# main.net
KiCad netlist of a schematic drawn in Altium Designer
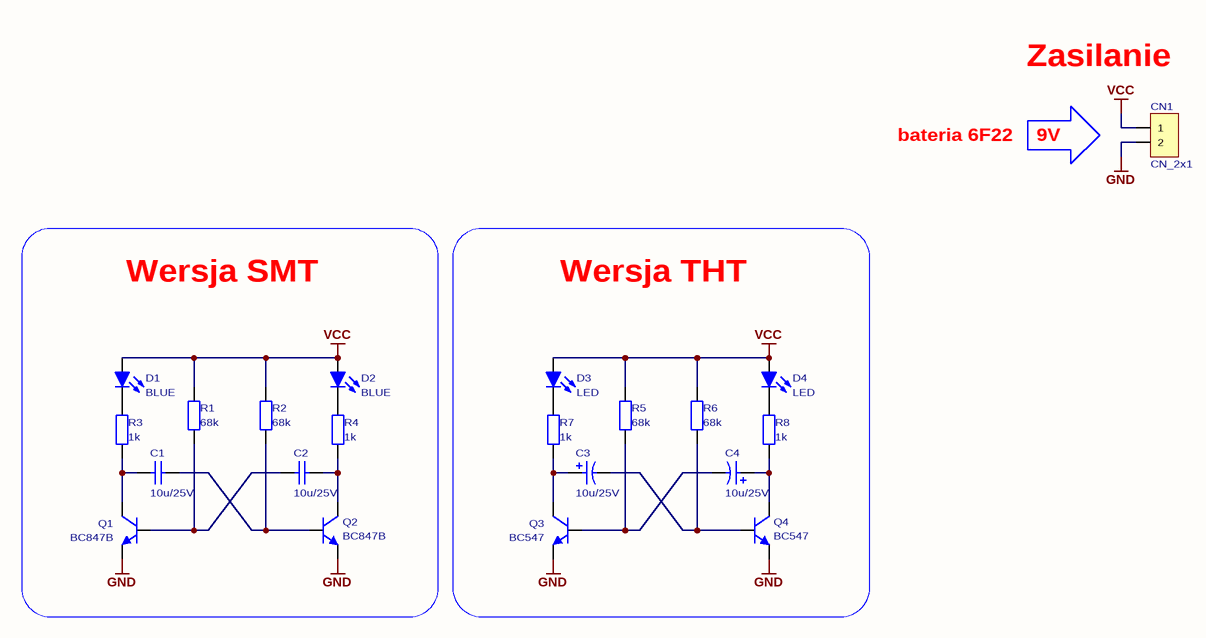
[diagram p0: main.SchDoc]

(export (version "E")
  (design (tool "Eeschema 10.0.6"))
  (components
    (comp (ref "C1")
      (value "10u/25V")
      (footprint "C1206")
      (description "Capacitor")
      (libsource (lib "capacitors") (part "Cap"))
    )
    (comp (ref "C2")
      (value "10u/25V")
      (footprint "C1206")
      (description "Capacitor")
      (libsource (lib "capacitors") (part "Cap"))
    )
    (comp (ref "C3")
      (value "10u/25V")
      (footprint "CE5x11-2")
      (description "Polarized Capacitor")
      (libsource (lib "capacitors") (part "Cap Pol"))
    )
    (comp (ref "C4")
      (value "10u/25V")
      (footprint "CE5x11-2")
      (description "Polarized Capacitor")
      (libsource (lib "capacitors") (part "Cap Pol"))
    )
    (comp (ref "CN1") (value "CN_2x1") (footprint "GP_2x1") (libsource (lib "goldpin_male") (part "CN_2x1")))
    (comp (ref "D1")
      (value "BLUE")
      (footprint "LED1206B")
      (description "BLUE LED")
      (libsource (lib "leds") (part "LED_BLUE"))
    )
    (comp (ref "D2")
      (value "BLUE")
      (footprint "LED1206B")
      (description "BLUE LED")
      (libsource (lib "leds") (part "LED_BLUE"))
    )
    (comp (ref "D3")
      (value "LED")
      (footprint "LED-Polarized")
      (description "Typical RED, GREEN, YELLOW, AMBER GaAs LED")
      (libsource (lib "leds") (part "LED"))
    )
    (comp (ref "D4")
      (value "LED")
      (footprint "LED-Polarized")
      (description "Typical RED, GREEN, YELLOW, AMBER GaAs LED")
      (libsource (lib "leds") (part "LED"))
    )
    (comp (ref "Q1")
      (value "BC847B")
      (footprint "SOT-23")
      (description "NPN General Purpose Transistor (VCE=45V, IC=100mA, HFE=200-450)")
      (libsource (lib "transistors_bjt") (part "BC847B"))
    )
    (comp (ref "Q2")
      (value "BC847B")
      (footprint "SOT-23")
      (description "NPN General Purpose Transistor (VCE=45V, IC=100mA, HFE=200-450)")
      (libsource (lib "transistors_bjt") (part "BC847B"))
    )
    (comp (ref "Q3")
      (value "BC547")
      (footprint "TO-92A")
      (description "NPN General Purpose Transistor (VCE=45V, IC=100mA)")
      (libsource (lib "transistors_bjt") (part "BC547"))
    )
    (comp (ref "Q4")
      (value "BC547")
      (footprint "TO-92A")
      (description "NPN General Purpose Transistor (VCE=45V, IC=100mA)")
      (libsource (lib "transistors_bjt") (part "BC547"))
    )
    (comp (ref "R1")
      (value "68k")
      (footprint "R1206")
      (description "Resistor")
      (libsource (lib "") (part "Res_1"))
    )
    (comp (ref "R2")
      (value "68k")
      (footprint "R1206")
      (description "Resistor")
      (libsource (lib "") (part "Res_1"))
    )
    (comp (ref "R3")
      (value "1k")
      (footprint "R1206")
      (description "Resistor")
      (libsource (lib "") (part "Res_1"))
    )
    (comp (ref "R4")
      (value "1k")
      (footprint "R1206")
      (description "Resistor")
      (libsource (lib "") (part "Res_1"))
    )
    (comp (ref "R5")
      (value "68k")
      (footprint "RES10.35-6.8X2.8")
      (description "Resistor")
      (libsource (lib "resistors") (part "Res"))
    )
    (comp (ref "R6")
      (value "68k")
      (footprint "RES10.35-6.8X2.8")
      (description "Resistor")
      (libsource (lib "resistors") (part "Res"))
    )
    (comp (ref "R7")
      (value "1k")
      (footprint "RES10.35-6.8X2.8")
      (description "Resistor")
      (libsource (lib "resistors") (part "Res"))
    )
    (comp (ref "R8")
      (value "1k")
      (footprint "RES10.35-6.8X2.8")
      (description "Resistor")
      (libsource (lib "resistors") (part "Res"))
    )
  )
  (nets
    (net (code "1") (name "GND") (class "Default")
      (node (ref "CN1") (pin "2") (pinfunction "2_2") (pintype "passive"))
      (node (ref "Q1") (pin "2") (pinfunction "E_2") (pintype "passive"))
      (node (ref "Q2") (pin "2") (pinfunction "E_2") (pintype "passive"))
      (node (ref "Q3") (pin "3") (pinfunction "E_3") (pintype "passive"))
      (node (ref "Q4") (pin "3") (pinfunction "E_3") (pintype "passive"))
    )
    (net (code "2") (name "Net-(D1-K)") (class "Default")
      (node (ref "D1") (pin "2") (pinfunction "K_2") (pintype "passive"))
      (node (ref "R3") (pin "1") (pinfunction "1_1") (pintype "passive"))
    )
    (net (code "3") (name "Net-(D2-K)") (class "Default")
      (node (ref "D2") (pin "2") (pinfunction "K_2") (pintype "passive"))
      (node (ref "R4") (pin "1") (pinfunction "1_1") (pintype "passive"))
    )
    (net (code "4") (name "Net-(D3-K)") (class "Default")
      (node (ref "D3") (pin "2") (pinfunction "K_2") (pintype "passive"))
      (node (ref "R7") (pin "2") (pinfunction "2_2") (pintype "passive"))
    )
    (net (code "5") (name "Net-(D4-K)") (class "Default")
      (node (ref "D4") (pin "2") (pinfunction "K_2") (pintype "passive"))
      (node (ref "R8") (pin "2") (pinfunction "2_2") (pintype "passive"))
    )
    (net (code "6") (name "Net-(Q1-B)") (class "Default")
      (node (ref "C2") (pin "1") (pinfunction "1_1") (pintype "passive"))
      (node (ref "Q1") (pin "1") (pinfunction "B_1") (pintype "passive"))
      (node (ref "R1") (pin "2") (pinfunction "2_2") (pintype "passive"))
    )
    (net (code "7") (name "Net-(Q1-C)") (class "Default")
      (node (ref "C1") (pin "1") (pinfunction "1_1") (pintype "passive"))
      (node (ref "Q1") (pin "3") (pinfunction "C_3") (pintype "passive"))
      (node (ref "R3") (pin "2") (pinfunction "2_2") (pintype "passive"))
    )
    (net (code "8") (name "Net-(Q2-B)") (class "Default")
      (node (ref "C1") (pin "2") (pinfunction "2_2") (pintype "passive"))
      (node (ref "Q2") (pin "1") (pinfunction "B_1") (pintype "passive"))
      (node (ref "R2") (pin "2") (pinfunction "2_2") (pintype "passive"))
    )
    (net (code "9") (name "Net-(Q2-C)") (class "Default")
      (node (ref "C2") (pin "2") (pinfunction "2_2") (pintype "passive"))
      (node (ref "Q2") (pin "3") (pinfunction "C_3") (pintype "passive"))
      (node (ref "R4") (pin "2") (pinfunction "2_2") (pintype "passive"))
    )
    (net (code "10") (name "Net-(Q3-B)") (class "Default")
      (node (ref "C4") (pin "2") (pinfunction "2_2") (pintype "passive"))
      (node (ref "Q3") (pin "2") (pinfunction "B_2") (pintype "passive"))
      (node (ref "R5") (pin "1") (pinfunction "1_1") (pintype "passive"))
    )
    (net (code "11") (name "Net-(Q3-C)") (class "Default")
      (node (ref "C3") (pin "1") (pinfunction "1_1") (pintype "passive"))
      (node (ref "Q3") (pin "1") (pinfunction "C_1") (pintype "passive"))
      (node (ref "R7") (pin "1") (pinfunction "1_1") (pintype "passive"))
    )
    (net (code "12") (name "Net-(Q4-B)") (class "Default")
      (node (ref "C3") (pin "2") (pinfunction "2_2") (pintype "passive"))
      (node (ref "Q4") (pin "2") (pinfunction "B_2") (pintype "passive"))
      (node (ref "R6") (pin "1") (pinfunction "1_1") (pintype "passive"))
    )
    (net (code "13") (name "Net-(Q4-C)") (class "Default")
      (node (ref "C4") (pin "1") (pinfunction "1_1") (pintype "passive"))
      (node (ref "Q4") (pin "1") (pinfunction "C_1") (pintype "passive"))
      (node (ref "R8") (pin "1") (pinfunction "1_1") (pintype "passive"))
    )
    (net (code "14") (name "VCC") (class "Default")
      (node (ref "CN1") (pin "1") (pinfunction "1_1") (pintype "passive"))
      (node (ref "D1") (pin "1") (pinfunction "A_1") (pintype "passive"))
      (node (ref "D2") (pin "1") (pinfunction "A_1") (pintype "passive"))
      (node (ref "D3") (pin "1") (pinfunction "A_1") (pintype "passive"))
      (node (ref "D4") (pin "1") (pinfunction "A_1") (pintype "passive"))
      (node (ref "R1") (pin "1") (pinfunction "1_1") (pintype "passive"))
      (node (ref "R2") (pin "1") (pinfunction "1_1") (pintype "passive"))
      (node (ref "R5") (pin "2") (pinfunction "2_2") (pintype "passive"))
      (node (ref "R6") (pin "2") (pinfunction "2_2") (pintype "passive"))
    )
  )
)
